# V-00386-01.net
KiCad netlist of a schematic drawn in EAGLE
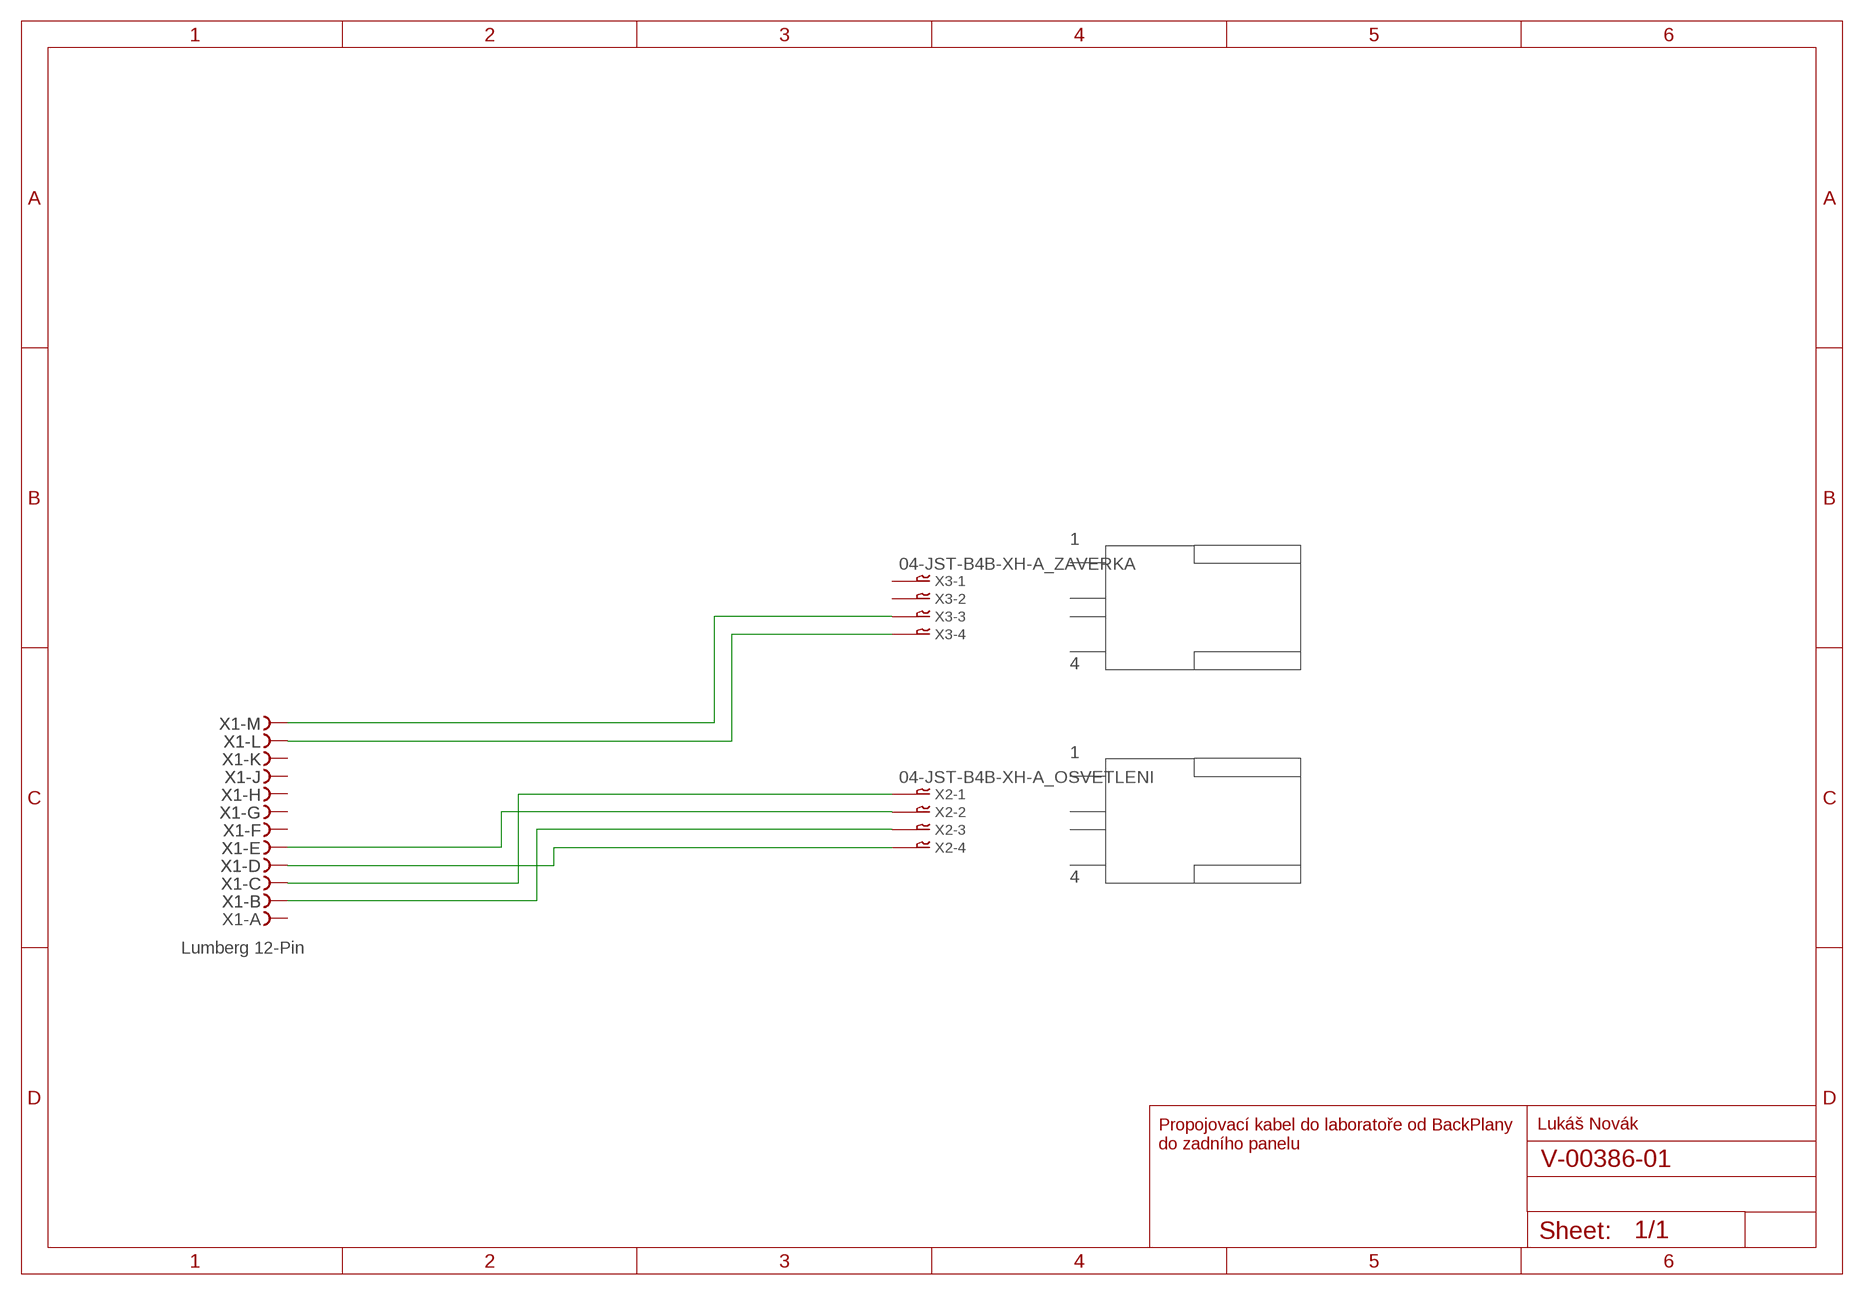
[diagram p0: schematic, sheet 1]

(export (version "E")
  (design (tool "Eeschema 10.0.6"))
  (components
    (comp (ref "X1")
      (value "LU12MP")
      (footprint "eagle-import:LU12MP")
      (libsource (lib "eagle-import") (part "LU12MP"))
    )
    (comp (ref "X2")
      (value "04-JST-B4B-XH-A_OSVETLENI")
      (footprint "eagle-import:B4B-XH")
      (libsource (lib "eagle-import") (part "04-JST-B4B-XH-A"))
    )
    (comp (ref "X3")
      (value "04-JST-B4B-XH-A_ZAVERKA")
      (footprint "eagle-import:B4B-XH")
      (libsource (lib "eagle-import") (part "04-JST-B4B-XH-A"))
    )
  )
  (nets
    (net (code "1") (name "Net-(X1B-F)") (class "Default")
      (node (ref "X1") (pin "B") (pinfunction "F_B") (pintype "passive"))
      (node (ref "X2") (pin "P$3") (pinfunction "1_P$3") (pintype "passive"))
    )
    (net (code "2") (name "Net-(X1C-F)") (class "Default")
      (node (ref "X1") (pin "C") (pinfunction "F_C") (pintype "passive"))
      (node (ref "X2") (pin "P$1") (pinfunction "1_P$1") (pintype "passive"))
    )
    (net (code "3") (name "Net-(X1D-F)") (class "Default")
      (node (ref "X1") (pin "D") (pinfunction "F_D") (pintype "passive"))
      (node (ref "X2") (pin "P$4") (pinfunction "1_P$4") (pintype "passive"))
    )
    (net (code "4") (name "Net-(X1E-F)") (class "Default")
      (node (ref "X1") (pin "E") (pinfunction "F_E") (pintype "passive"))
      (node (ref "X2") (pin "P$2") (pinfunction "1_P$2") (pintype "passive"))
    )
    (net (code "5") (name "Net-(X1K-F)") (class "Default")
      (node (ref "X1") (pin "L") (pinfunction "F_L") (pintype "passive"))
      (node (ref "X3") (pin "P$4") (pinfunction "1_P$4") (pintype "passive"))
    )
    (net (code "6") (name "Net-(X1L-F)") (class "Default")
      (node (ref "X1") (pin "M") (pinfunction "F_M") (pintype "passive"))
      (node (ref "X3") (pin "P$3") (pinfunction "1_P$3") (pintype "passive"))
    )
    (net (code "7") (name "unconnected-(X1-PadF)") (class "Default")
      (node (ref "X1") (pin "F") (pinfunction "F_F") (pintype "passive"))
    )
    (net (code "8") (name "unconnected-(X1A-F-PadA)") (class "Default")
      (node (ref "X1") (pin "A") (pinfunction "F_A") (pintype "passive"))
    )
    (net (code "9") (name "unconnected-(X1G-F-PadG)") (class "Default")
      (node (ref "X1") (pin "G") (pinfunction "F_G") (pintype "passive"))
    )
    (net (code "10") (name "unconnected-(X1H-F-PadH)") (class "Default")
      (node (ref "X1") (pin "H") (pinfunction "F_H") (pintype "passive"))
    )
    (net (code "11") (name "unconnected-(X1I-F-PadJ)") (class "Default")
      (node (ref "X1") (pin "J") (pinfunction "F_J") (pintype "passive"))
    )
    (net (code "12") (name "unconnected-(X1J-F-PadK)") (class "Default")
      (node (ref "X1") (pin "K") (pinfunction "F_K") (pintype "passive"))
    )
    (net (code "13") (name "unconnected-(X3A-1-PadP$1)") (class "Default")
      (node (ref "X3") (pin "P$1") (pinfunction "1_P$1") (pintype "passive"))
    )
    (net (code "14") (name "unconnected-(X3B-1-PadP$2)") (class "Default")
      (node (ref "X3") (pin "P$2") (pinfunction "1_P$2") (pintype "passive"))
    )
  )
)
